# 4_downstream_power.net
KiCad netlist of a schematic drawn in Altium Designer
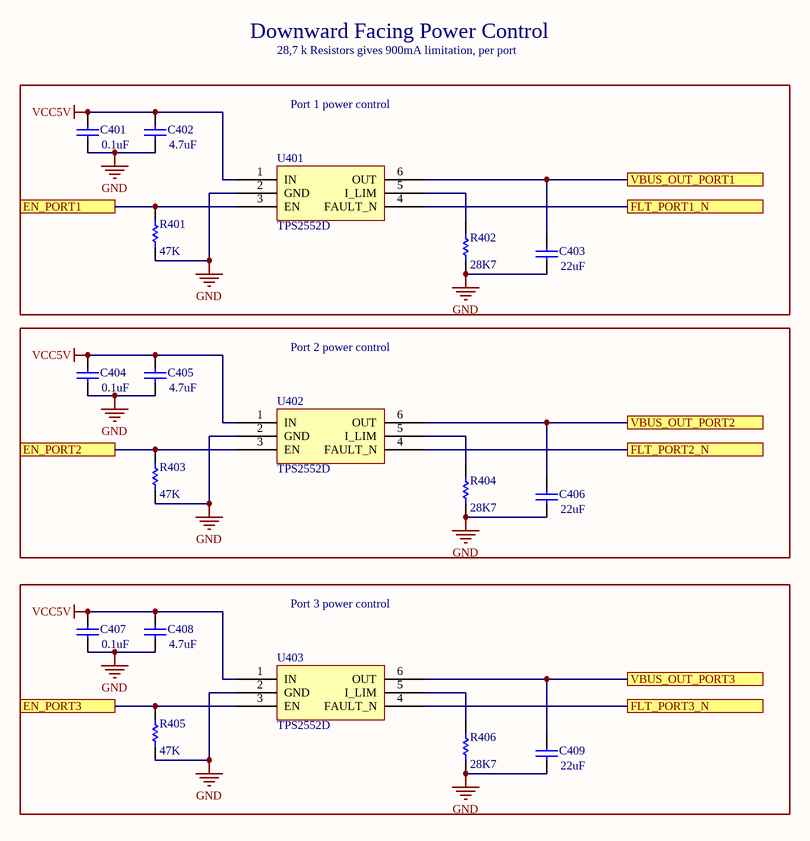
[diagram p0: 4_downstream_power.SchDoc]

(export (version "E")
  (design (tool "Eeschema 10.0.6"))
  (components
    (comp (ref "C401")
      (value "0.1uF")
      (footprint "C0603[1608]")
      (description "Capacitor")
      (fields (field (name "MFG") "KEMET") (field (name "LCSC PART #") "C14663"))
      (libsource (lib "Miscellaneous Devices") (part "Cap"))
    )
    (comp (ref "C402")
      (value "4.7uF")
      (footprint "C1206[3216]")
      (description "Capacitor")
      (fields (field (name "MFG") "KEMET") (field (name "LCSC PART #") "C29823"))
      (libsource (lib "Miscellaneous Devices") (part "Cap"))
    )
    (comp (ref "C403")
      (value "22uF")
      (footprint "C1206[3216]")
      (description "Capacitor")
      (fields (field (name "MFG") "KEMET") (field (name "LCSC PART #") "C45783"))
      (libsource (lib "Miscellaneous Devices") (part "Cap"))
    )
    (comp (ref "C404")
      (value "0.1uF")
      (footprint "C0603[1608]")
      (description "Capacitor")
      (fields (field (name "MFG") "KEMET") (field (name "LCSC PART #") "C14663"))
      (libsource (lib "Miscellaneous Devices") (part "Cap"))
    )
    (comp (ref "C405")
      (value "4.7uF")
      (footprint "C1206[3216]")
      (description "Capacitor")
      (fields (field (name "MFG") "KEMET") (field (name "LCSC PART #") "C29823"))
      (libsource (lib "Miscellaneous Devices") (part "Cap"))
    )
    (comp (ref "C406")
      (value "22uF")
      (footprint "C1206[3216]")
      (description "Capacitor")
      (fields (field (name "MFG") "KEMET") (field (name "LCSC PART #") "C45783"))
      (libsource (lib "Miscellaneous Devices") (part "Cap"))
    )
    (comp (ref "C407")
      (value "0.1uF")
      (footprint "C0603[1608]")
      (description "Capacitor")
      (fields (field (name "MFG") "KEMET") (field (name "LCSC PART #") "C14663"))
      (libsource (lib "Miscellaneous Devices") (part "Cap"))
    )
    (comp (ref "C408")
      (value "4.7uF")
      (footprint "C1206[3216]")
      (description "Capacitor")
      (fields (field (name "MFG") "KEMET") (field (name "LCSC PART #") "C29823"))
      (libsource (lib "Miscellaneous Devices") (part "Cap"))
    )
    (comp (ref "C409")
      (value "22uF")
      (footprint "C1206[3216]")
      (description "Capacitor")
      (fields (field (name "MFG") "KEMET") (field (name "LCSC PART #") "C45783"))
      (libsource (lib "Miscellaneous Devices") (part "Cap"))
    )
    (comp (ref "R401")
      (value "47K")
      (footprint "R0603[1608]")
      (description "Resistor")
      (fields (field (name "MFG") "Vishay Dale") (field (name "LCSC PART #") "C25819"))
      (libsource (lib "Miscellaneous Devices") (part "Res1"))
    )
    (comp (ref "R402")
      (value "28K7")
      (footprint "R0603[1608]")
      (description "Resistor")
      (fields (field (name "MFG") "Vishay Dale") (field (name "LCSC PART #") "C22928"))
      (libsource (lib "Miscellaneous Devices") (part "Res1"))
    )
    (comp (ref "R403")
      (value "47K")
      (footprint "R0603[1608]")
      (description "Resistor")
      (fields (field (name "MFG") "Vishay Dale") (field (name "LCSC PART #") "C25819"))
      (libsource (lib "Miscellaneous Devices") (part "Res1"))
    )
    (comp (ref "R404")
      (value "28K7")
      (footprint "R0603[1608]")
      (description "Resistor")
      (fields (field (name "MFG") "Vishay Dale") (field (name "LCSC PART #") "C22928"))
      (libsource (lib "Miscellaneous Devices") (part "Res1"))
    )
    (comp (ref "R405")
      (value "47K")
      (footprint "R0603[1608]")
      (description "Resistor")
      (fields (field (name "MFG") "Vishay Dale") (field (name "LCSC PART #") "C25819"))
      (libsource (lib "Miscellaneous Devices") (part "Res1"))
    )
    (comp (ref "R406")
      (value "28K7")
      (footprint "R0603[1608]")
      (description "Resistor")
      (fields (field (name "MFG") "Vishay Dale") (field (name "LCSC PART #") "C22928"))
      (libsource (lib "Miscellaneous Devices") (part "Res1"))
    )
    (comp (ref "U401")
      (value "TPS2552D")
      (footprint "SOT-23-6")
      (fields
        (field (name "MFG") "Texas Instruments")
        (field (name "LCSC PART #") "C84988")
        (field (name "MRF.PART") "BD2243G-GTR")
      )
      (libsource (lib "lib") (part "TPS2552D"))
    )
    (comp (ref "U402")
      (value "TPS2552D")
      (footprint "SOT-23-6")
      (fields
        (field (name "MFG") "Texas Instruments")
        (field (name "LCSC PART #") "C84988")
        (field (name "MRF.PART") "BD2243G-GTR")
      )
      (libsource (lib "lib") (part "TPS2552D"))
    )
    (comp (ref "U403")
      (value "TPS2552D")
      (footprint "SOT-23-6")
      (fields
        (field (name "MFG") "Texas Instruments")
        (field (name "LCSC PART #") "C84988")
        (field (name "MRF.PART") "BD2243G-GTR")
      )
      (libsource (lib "lib") (part "TPS2552D"))
    )
  )
  (nets
    (net (code "1") (name "/EN_PORT1") (class "Default")
      (node (ref "R401") (pin "1") (pinfunction "1_1") (pintype "passive"))
      (node (ref "U401") (pin "3") (pinfunction "EN_3") (pintype "passive"))
    )
    (net (code "2") (name "/EN_PORT2") (class "Default")
      (node (ref "R403") (pin "1") (pinfunction "1_1") (pintype "passive"))
      (node (ref "U402") (pin "3") (pinfunction "EN_3") (pintype "passive"))
    )
    (net (code "3") (name "/EN_PORT3") (class "Default")
      (node (ref "R405") (pin "1") (pinfunction "1_1") (pintype "passive"))
      (node (ref "U403") (pin "3") (pinfunction "EN_3") (pintype "passive"))
    )
    (net (code "4") (name "/FLT_PORT1_N") (class "Default")
      (node (ref "U401") (pin "4") (pinfunction "FAULT_N_4") (pintype "passive"))
    )
    (net (code "5") (name "/FLT_PORT2_N") (class "Default")
      (node (ref "U402") (pin "4") (pinfunction "FAULT_N_4") (pintype "passive"))
    )
    (net (code "6") (name "/FLT_PORT3_N") (class "Default")
      (node (ref "U403") (pin "4") (pinfunction "FAULT_N_4") (pintype "passive"))
    )
    (net (code "7") (name "/VBUS_OUT_PORT1") (class "Default")
      (node (ref "C403") (pin "2") (pinfunction "2_2") (pintype "passive"))
      (node (ref "U401") (pin "6") (pinfunction "OUT_6") (pintype "passive"))
    )
    (net (code "8") (name "/VBUS_OUT_PORT2") (class "Default")
      (node (ref "C406") (pin "2") (pinfunction "2_2") (pintype "passive"))
      (node (ref "U402") (pin "6") (pinfunction "OUT_6") (pintype "passive"))
    )
    (net (code "9") (name "/VBUS_OUT_PORT3") (class "Default")
      (node (ref "C409") (pin "2") (pinfunction "2_2") (pintype "passive"))
      (node (ref "U403") (pin "6") (pinfunction "OUT_6") (pintype "passive"))
    )
    (net (code "10") (name "GND") (class "Default")
      (node (ref "C401") (pin "1") (pinfunction "1_1") (pintype "passive"))
      (node (ref "C402") (pin "1") (pinfunction "1_1") (pintype "passive"))
      (node (ref "C403") (pin "1") (pinfunction "1_1") (pintype "passive"))
      (node (ref "C404") (pin "1") (pinfunction "1_1") (pintype "passive"))
      (node (ref "C405") (pin "1") (pinfunction "1_1") (pintype "passive"))
      (node (ref "C406") (pin "1") (pinfunction "1_1") (pintype "passive"))
      (node (ref "C407") (pin "1") (pinfunction "1_1") (pintype "passive"))
      (node (ref "C408") (pin "1") (pinfunction "1_1") (pintype "passive"))
      (node (ref "C409") (pin "1") (pinfunction "1_1") (pintype "passive"))
      (node (ref "R401") (pin "2") (pinfunction "2_2") (pintype "passive"))
      (node (ref "R402") (pin "2") (pinfunction "2_2") (pintype "passive"))
      (node (ref "R403") (pin "2") (pinfunction "2_2") (pintype "passive"))
      (node (ref "R404") (pin "2") (pinfunction "2_2") (pintype "passive"))
      (node (ref "R405") (pin "2") (pinfunction "2_2") (pintype "passive"))
      (node (ref "R406") (pin "2") (pinfunction "2_2") (pintype "passive"))
      (node (ref "U401") (pin "2") (pinfunction "GND_2") (pintype "passive"))
      (node (ref "U402") (pin "2") (pinfunction "GND_2") (pintype "passive"))
      (node (ref "U403") (pin "2") (pinfunction "GND_2") (pintype "passive"))
    )
    (net (code "11") (name "Net-(U401-I_LIM)") (class "Default")
      (node (ref "R402") (pin "1") (pinfunction "1_1") (pintype "passive"))
      (node (ref "U401") (pin "5") (pinfunction "I_LIM_5") (pintype "passive"))
    )
    (net (code "12") (name "Net-(U402-I_LIM)") (class "Default")
      (node (ref "R404") (pin "1") (pinfunction "1_1") (pintype "passive"))
      (node (ref "U402") (pin "5") (pinfunction "I_LIM_5") (pintype "passive"))
    )
    (net (code "13") (name "Net-(U403-I_LIM)") (class "Default")
      (node (ref "R406") (pin "1") (pinfunction "1_1") (pintype "passive"))
      (node (ref "U403") (pin "5") (pinfunction "I_LIM_5") (pintype "passive"))
    )
    (net (code "14") (name "VCC5V") (class "Default")
      (node (ref "C401") (pin "2") (pinfunction "2_2") (pintype "passive"))
      (node (ref "C402") (pin "2") (pinfunction "2_2") (pintype "passive"))
      (node (ref "C404") (pin "2") (pinfunction "2_2") (pintype "passive"))
      (node (ref "C405") (pin "2") (pinfunction "2_2") (pintype "passive"))
      (node (ref "C407") (pin "2") (pinfunction "2_2") (pintype "passive"))
      (node (ref "C408") (pin "2") (pinfunction "2_2") (pintype "passive"))
      (node (ref "U401") (pin "1") (pinfunction "IN_1") (pintype "passive"))
      (node (ref "U402") (pin "1") (pinfunction "IN_1") (pintype "passive"))
      (node (ref "U403") (pin "1") (pinfunction "IN_1") (pintype "passive"))
    )
  )
)
